# OSO-MISC-22-005_UART_Breakout.net
KiCad netlist of a schematic drawn in EAGLE
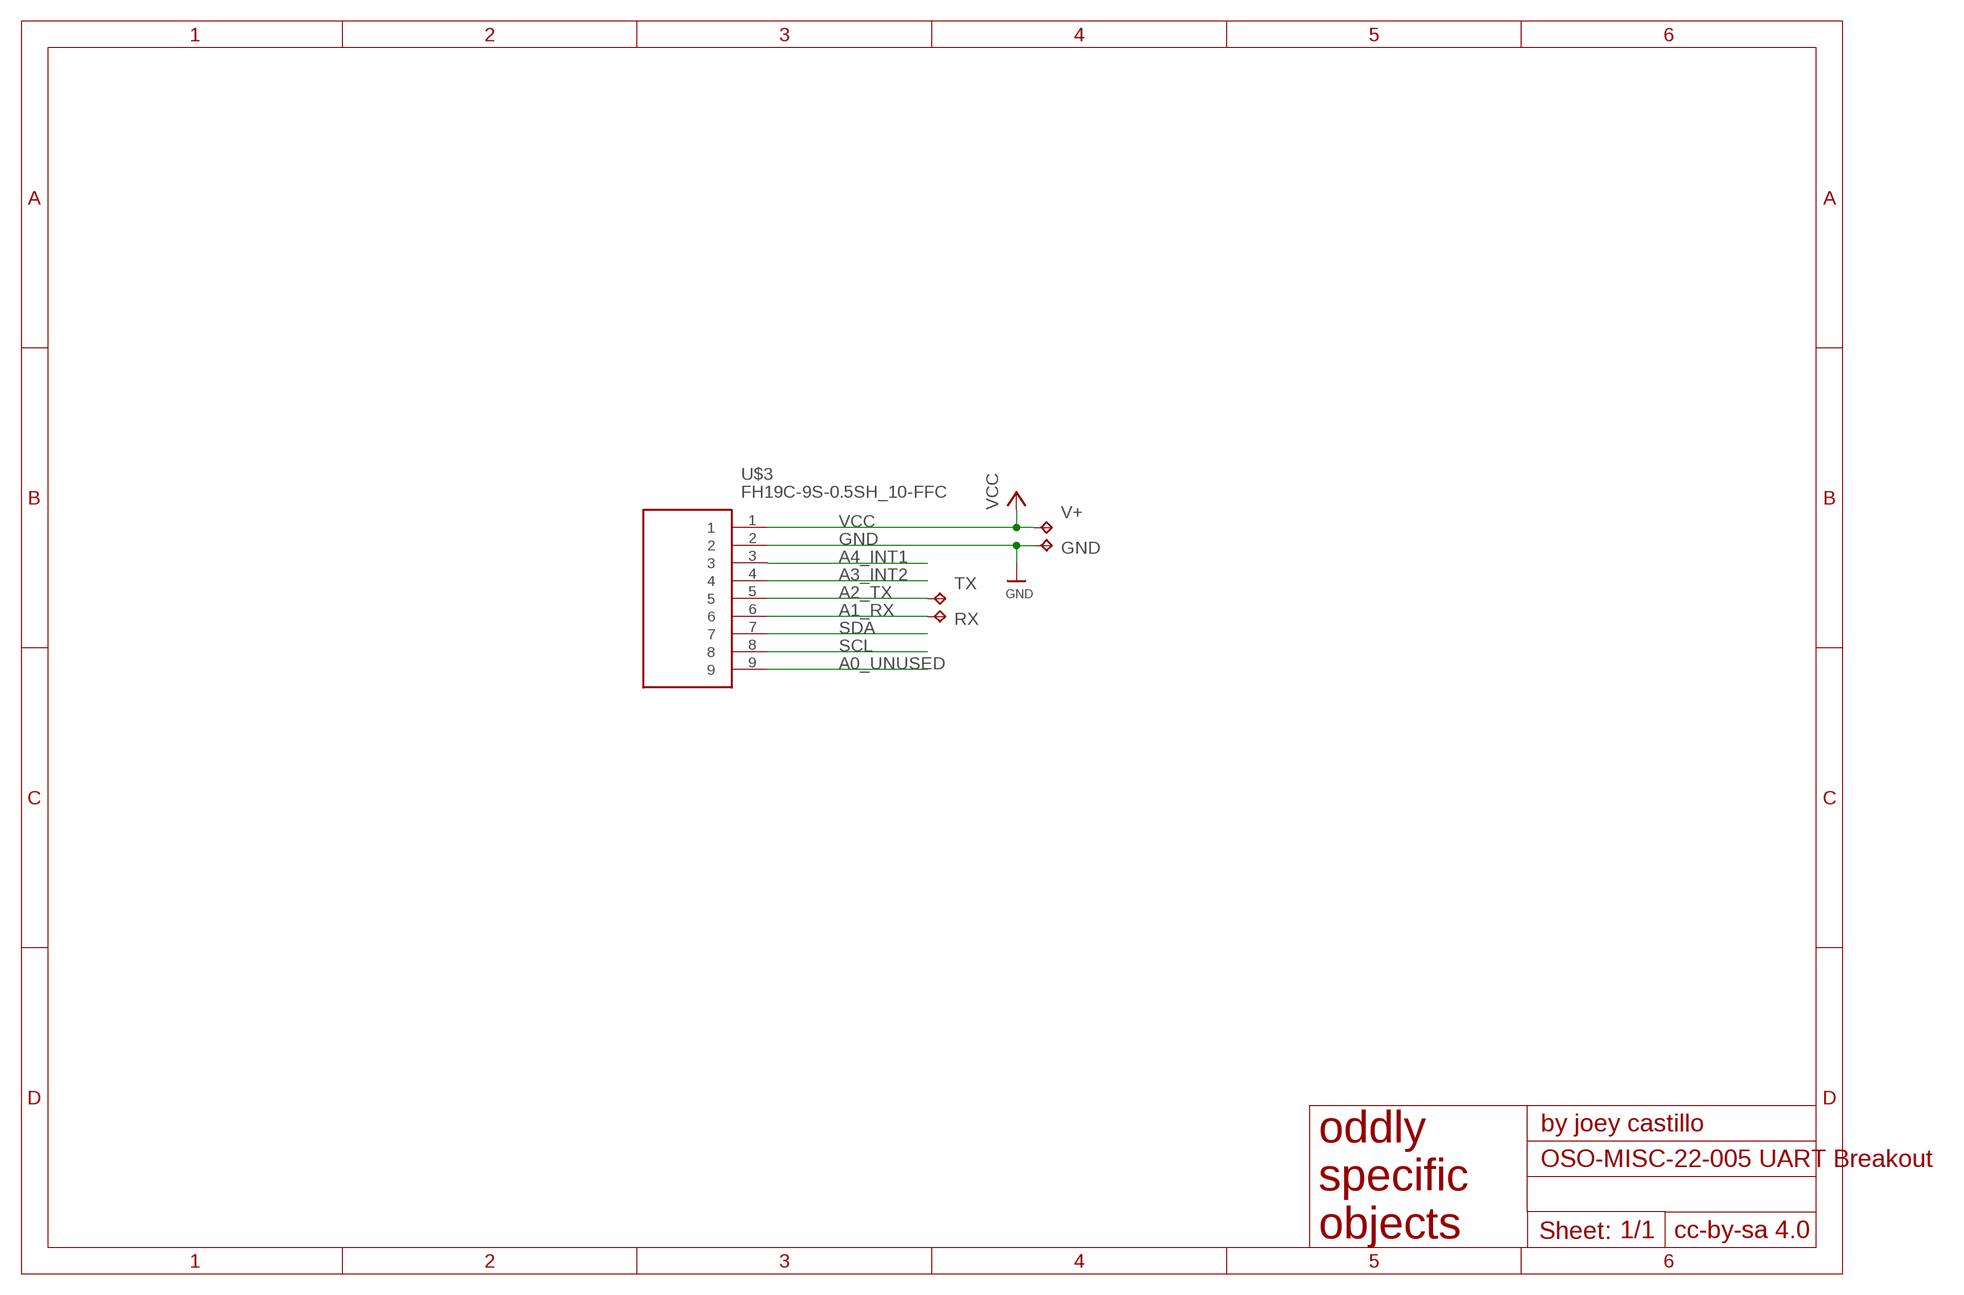
[diagram p0: schematic, sheet 1]

(export (version "E")
  (design (tool "Eeschema 10.0.6"))
  (components
    (comp (ref "GND")
      (value "TPTP20R")
      (footprint "eagle-import:TP20R")
      (libsource (lib "eagle-import") (part "TPTP20R"))
    )
    (comp (ref "RX")
      (value "TPTP20R")
      (footprint "eagle-import:TP20R")
      (libsource (lib "eagle-import") (part "TPTP20R"))
    )
    (comp (ref "TX")
      (value "TPTP20R")
      (footprint "eagle-import:TP20R")
      (libsource (lib "eagle-import") (part "TPTP20R"))
    )
    (comp (ref "U$3")
      (value "FH19C-9S-0.5SH_10-FFC")
      (footprint "eagle-import:FH19C9S05SH10-FFC")
      (libsource (lib "eagle-import") (part "FH19C-9S-0.5SH_10-FFC"))
    )
    (comp (ref "V+")
      (value "TPTP20R")
      (footprint "eagle-import:TP20R")
      (libsource (lib "eagle-import") (part "TPTP20R"))
    )
  )
  (nets
    (net (code "1") (name "/A0_UNUSED") (class "Default")
      (node (ref "U$3") (pin "9") (pinfunction "9_9") (pintype "bidirectional"))
    )
    (net (code "2") (name "/A1_RX") (class "Default")
      (node (ref "RX") (pin "TP") (pinfunction "TP_TP") (pintype "input"))
      (node (ref "U$3") (pin "6") (pinfunction "6_6") (pintype "bidirectional"))
    )
    (net (code "3") (name "/A2_TX") (class "Default")
      (node (ref "TX") (pin "TP") (pinfunction "TP_TP") (pintype "input"))
      (node (ref "U$3") (pin "5") (pinfunction "5_5") (pintype "bidirectional"))
    )
    (net (code "4") (name "/A3_INT2") (class "Default")
      (node (ref "U$3") (pin "4") (pinfunction "4_4") (pintype "bidirectional"))
    )
    (net (code "5") (name "/A4_INT1") (class "Default")
      (node (ref "U$3") (pin "3") (pinfunction "3_3") (pintype "bidirectional"))
    )
    (net (code "6") (name "/SCL") (class "Default")
      (node (ref "U$3") (pin "8") (pinfunction "8_8") (pintype "bidirectional"))
    )
    (net (code "7") (name "/SDA") (class "Default")
      (node (ref "U$3") (pin "7") (pinfunction "7_7") (pintype "bidirectional"))
    )
    (net (code "8") (name "GND") (class "Default")
      (node (ref "GND") (pin "TP") (pinfunction "TP_TP") (pintype "input"))
      (node (ref "U$3") (pin "2") (pinfunction "2_2") (pintype "bidirectional"))
    )
    (net (code "9") (name "VCC") (class "Default")
      (node (ref "U$3") (pin "1") (pinfunction "1_1") (pintype "bidirectional"))
      (node (ref "V+") (pin "TP") (pinfunction "TP_TP") (pintype "input"))
    )
  )
)
